# Demo_Board_1_-_Schematic.net
KiCad netlist of a schematic drawn in Altium Designer
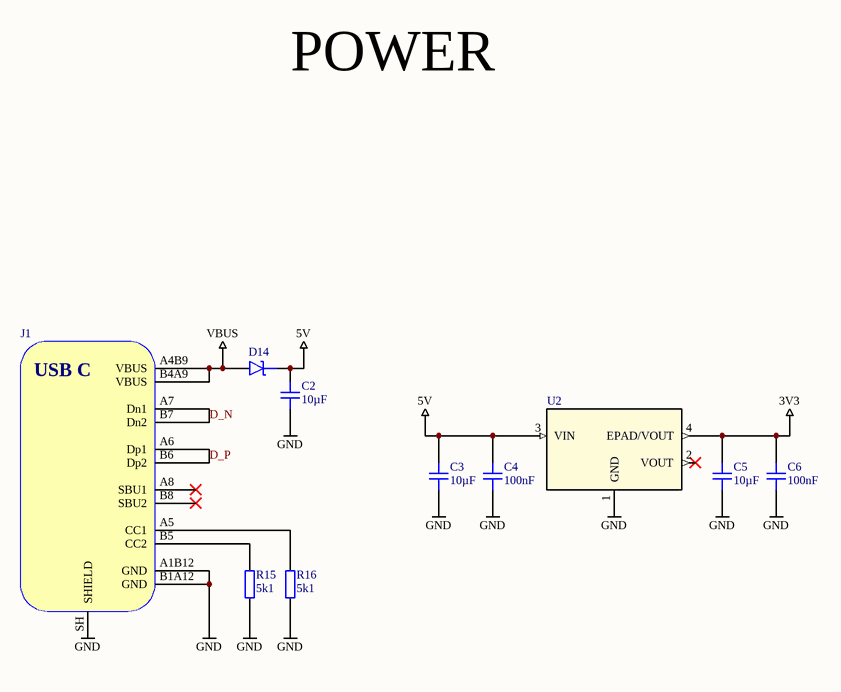
[diagram p0: Demo Board 1 - Schematic.SchDoc]

(export (version "E")
  (design (tool "Eeschema 10.0.6"))
  (components
    (comp (ref "C2")
      (value "10µF")
      (footprint "CAP_0805")
      (description "Capacitor SMD 0805")
      (libsource (lib "Auer Library") (part "CAP_0805"))
    )
    (comp (ref "C3")
      (value "10µF")
      (footprint "CAP_0805")
      (description "Capacitor SMD 0805")
      (libsource (lib "Auer Library") (part "CAP_0805"))
    )
    (comp (ref "C4")
      (value "100nF")
      (footprint "CAP_0603")
      (description "Capacitor SMD 0603")
      (libsource (lib "Auer Library") (part "CAP_0603"))
    )
    (comp (ref "C5")
      (value "10µF")
      (footprint "CAP_0805")
      (description "Capacitor SMD 0805")
      (libsource (lib "Auer Library") (part "CAP_0805"))
    )
    (comp (ref "C6")
      (value "100nF")
      (footprint "CAP_0603")
      (description "Capacitor SMD 0603")
      (libsource (lib "Auer Library") (part "CAP_0603"))
    )
    (comp (ref "D14")
      (value "MS2A40LWS")
      (footprint "SOD-323")
      (description "Diode Schottky SMD SOD-323, MS2A40LWS")
      (libsource (lib "Auer Library") (part "D_SCHOTTKY_SOD_323"))
    )
    (comp (ref "J1")
      (value "USB4105-GF-A-060")
      (footprint "USB4105-GF-A-060")
      (description "USB Connector Type C SMT 12 Pin")
      (fields (field (name "MANUFACTURER") "GCT"))
      (libsource (lib "Auer Library") (part "USB4105-GF-A-060"))
    )
    (comp (ref "R15")
      (value "5k1")
      (footprint "RES_0402")
      (description "Resistor SMD 0402")
      (libsource (lib "Auer Library") (part "RES_0402"))
    )
    (comp (ref "R16")
      (value "5k1")
      (footprint "RES_0402")
      (description "Resistor SMD 0402")
      (libsource (lib "Auer Library") (part "RES_0402"))
    )
    (comp (ref "U2")
      (value "AMS1117-3.3")
      (footprint "SOT_AMS_ADS")
      (description "Description")
      (fields (field (name "COPYRIGHT") "Copyright (C) 2025 Ultra Librarian. All rights reserved."))
      (libsource (lib "AMS1117-3P3") (part "AMS1117-3.3"))
    )
  )
  (nets
    (net (code "1") (name "/D_N") (class "Default")
      (node (ref "J1") (pin "A7") (pinfunction "Dn1_A7") (pintype "passive"))
      (node (ref "J1") (pin "B7") (pinfunction "Dn2_B7") (pintype "passive"))
    )
    (net (code "2") (name "/D_P") (class "Default")
      (node (ref "J1") (pin "A6") (pinfunction "Dp1_A6") (pintype "passive"))
      (node (ref "J1") (pin "B6") (pinfunction "Dp2_B6") (pintype "passive"))
    )
    (net (code "3") (name "3V3") (class "Default")
      (node (ref "C5") (pin "2") (pinfunction "2_2") (pintype "passive"))
      (node (ref "C6") (pin "2") (pinfunction "2_2") (pintype "passive"))
      (node (ref "U2") (pin "4") (pinfunction "EPAD/VOUT_4") (pintype "output"))
    )
    (net (code "4") (name "5V") (class "Default")
      (node (ref "C2") (pin "2") (pinfunction "2_2") (pintype "passive"))
      (node (ref "C3") (pin "2") (pinfunction "2_2") (pintype "passive"))
      (node (ref "C4") (pin "2") (pinfunction "2_2") (pintype "passive"))
      (node (ref "D14") (pin "K") (pinfunction "K_K") (pintype "passive"))
      (node (ref "U2") (pin "3") (pinfunction "VIN_3") (pintype "input"))
    )
    (net (code "5") (name "GND") (class "Default")
      (node (ref "C2") (pin "1") (pinfunction "1_1") (pintype "passive"))
      (node (ref "C3") (pin "1") (pinfunction "1_1") (pintype "passive"))
      (node (ref "C4") (pin "1") (pinfunction "1_1") (pintype "passive"))
      (node (ref "C5") (pin "1") (pinfunction "1_1") (pintype "passive"))
      (node (ref "C6") (pin "1") (pinfunction "1_1") (pintype "passive"))
      (node (ref "J1") (pin "A1B12") (pinfunction "GND_A1B12") (pintype "passive"))
      (node (ref "J1") (pin "B1A12") (pinfunction "GND_B1A12") (pintype "passive"))
      (node (ref "J1") (pin "SH") (pinfunction "SHIELD_SH") (pintype "passive"))
      (node (ref "R15") (pin "1") (pinfunction "1_1") (pintype "passive"))
      (node (ref "R16") (pin "1") (pinfunction "1_1") (pintype "passive"))
      (node (ref "U2") (pin "1") (pinfunction "GND_1") (pintype "power_in"))
    )
    (net (code "6") (name "Net-(J1-CC1)") (class "Default")
      (node (ref "J1") (pin "A5") (pinfunction "CC1_A5") (pintype "passive"))
      (node (ref "R16") (pin "2") (pinfunction "2_2") (pintype "passive"))
    )
    (net (code "7") (name "Net-(J1-CC2)") (class "Default")
      (node (ref "J1") (pin "B5") (pinfunction "CC2_B5") (pintype "passive"))
      (node (ref "R15") (pin "2") (pinfunction "2_2") (pintype "passive"))
    )
    (net (code "8") (name "VBUS") (class "Default")
      (node (ref "D14") (pin "A") (pinfunction "A_A") (pintype "passive"))
      (node (ref "J1") (pin "A4B9") (pinfunction "VBUS_A4B9") (pintype "passive"))
      (node (ref "J1") (pin "B4A9") (pinfunction "VBUS_B4A9") (pintype "passive"))
    )
    (net (code "9") (name "unconnected-(J1-SBU1-PadA8)") (class "Default")
      (node (ref "J1") (pin "A8") (pinfunction "SBU1_A8") (pintype "passive+no_connect"))
    )
    (net (code "10") (name "unconnected-(J1-SBU2-PadB8)") (class "Default")
      (node (ref "J1") (pin "B8") (pinfunction "SBU2_B8") (pintype "passive+no_connect"))
    )
    (net (code "11") (name "unconnected-(U2-VOUT-Pad2)") (class "Default")
      (node (ref "U2") (pin "2") (pinfunction "VOUT_2") (pintype "output+no_connect"))
    )
  )
)
